# Fyve_Sicks.net
KiCad netlist of a schematic drawn in EAGLE
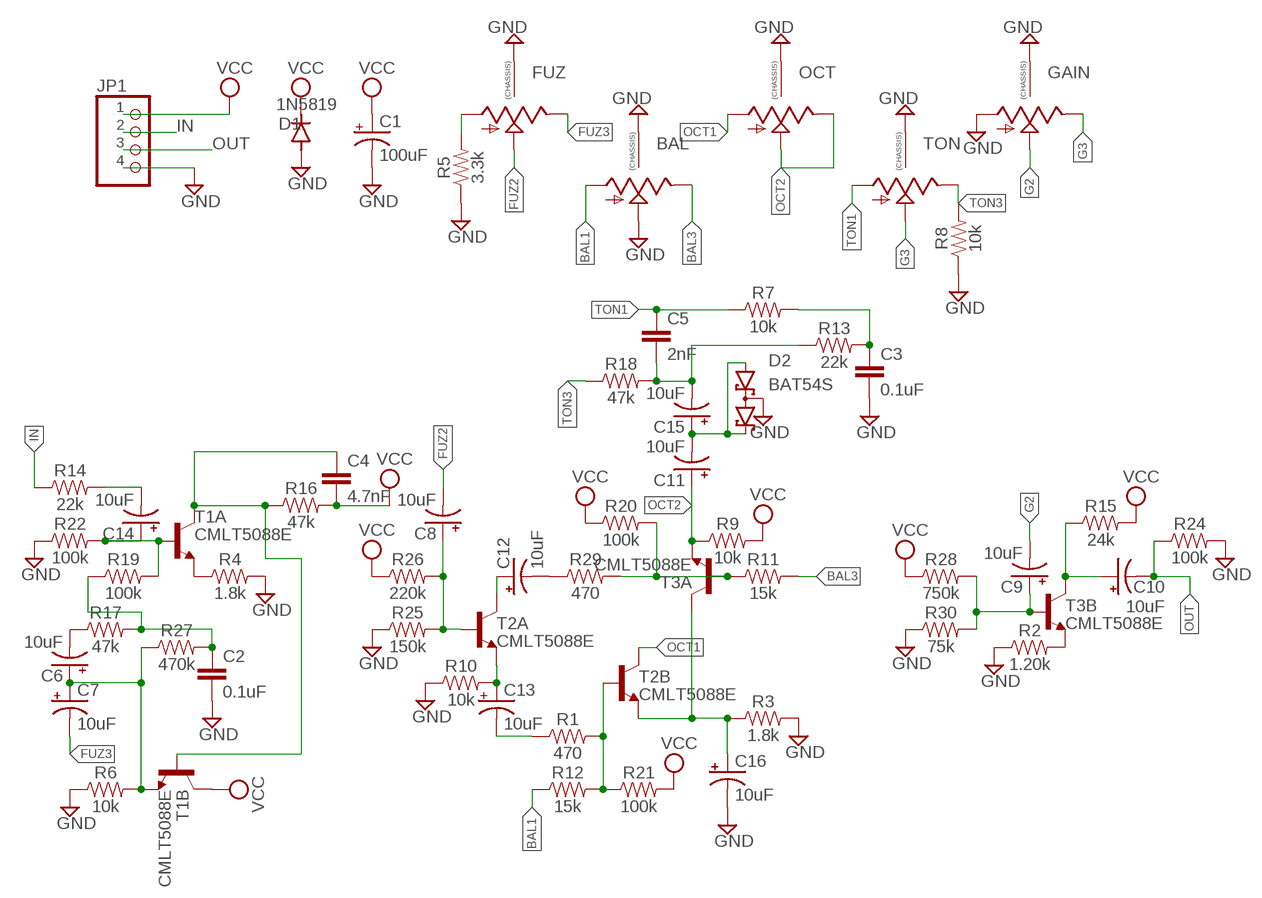
[diagram p0: schematic, sheet 1]

(export (version "E")
  (design (tool "Eeschema 10.0.6"))
  (components
    (comp (ref "BAL")
      (value "9MM_SNAP-IN_POT_CHASSIS")
      (footprint "eagle-import:9MM_SNAP-IN_POT")
      (libsource (lib "eagle-import") (part "9MM_SNAP-IN_POT_CHASSIS"))
    )
    (comp (ref "C1")
      (value "100uF")
      (footprint "eagle-import:PAN_B_SMD+THRU")
      (libsource (lib "eagle-import") (part "CAP_SMD+THRUPAN_B"))
    )
    (comp (ref "C2")
      (value "0.1uF")
      (footprint "eagle-import:0603")
      (libsource (lib "eagle-import") (part "0.1UF-0603-25V-(+80/-20%)"))
    )
    (comp (ref "C3")
      (value "0.1uF")
      (footprint "eagle-import:0603")
      (libsource (lib "eagle-import") (part "0.1UF-0603-25V-(+80/-20%)"))
    )
    (comp (ref "C4")
      (value "4.7nF")
      (footprint "eagle-import:0603")
      (libsource (lib "eagle-import") (part "4.7PF-0603-50V-5%"))
    )
    (comp (ref "C5")
      (value "2nF")
      (footprint "eagle-import:0603")
      (libsource (lib "eagle-import") (part "2.2NF/2200PF-0603-50V-10%"))
    )
    (comp (ref "C6")
      (value "10uF")
      (footprint "eagle-import:EIA3528")
      (libsource (lib "eagle-import") (part "10UF-POLAR-EIA3528-20V-10%(TANT)"))
    )
    (comp (ref "C7")
      (value "10uF")
      (footprint "eagle-import:EIA3528")
      (libsource (lib "eagle-import") (part "10UF-POLAR-EIA3528-20V-10%(TANT)"))
    )
    (comp (ref "C8")
      (value "10uF")
      (footprint "eagle-import:EIA3528")
      (libsource (lib "eagle-import") (part "10UF-POLAR-EIA3528-20V-10%(TANT)"))
    )
    (comp (ref "C9")
      (value "10uF")
      (footprint "eagle-import:EIA3528")
      (libsource (lib "eagle-import") (part "10UF-POLAR-EIA3528-20V-10%(TANT)"))
    )
    (comp (ref "C10")
      (value "10uF")
      (footprint "eagle-import:EIA3528")
      (libsource (lib "eagle-import") (part "10UF-POLAR-EIA3528-20V-10%(TANT)"))
    )
    (comp (ref "C11")
      (value "10uF")
      (footprint "eagle-import:EIA3528")
      (libsource (lib "eagle-import") (part "10UF-POLAR-EIA3528-20V-10%(TANT)"))
    )
    (comp (ref "C12")
      (value "10uF")
      (footprint "eagle-import:EIA3528")
      (libsource (lib "eagle-import") (part "10UF-POLAR-EIA3528-20V-10%(TANT)"))
    )
    (comp (ref "C13")
      (value "10uF")
      (footprint "eagle-import:EIA3528")
      (libsource (lib "eagle-import") (part "10UF-POLAR-EIA3528-20V-10%(TANT)"))
    )
    (comp (ref "C14")
      (value "10uF")
      (footprint "eagle-import:EIA3528")
      (libsource (lib "eagle-import") (part "10UF-POLAR-EIA3528-20V-10%(TANT)"))
    )
    (comp (ref "C15")
      (value "10uF")
      (footprint "eagle-import:EIA3528")
      (libsource (lib "eagle-import") (part "10UF-POLAR-EIA3528-20V-10%(TANT)"))
    )
    (comp (ref "C16")
      (value "10uF")
      (footprint "eagle-import:EIA3528")
      (libsource (lib "eagle-import") (part "10UF-POLAR-EIA3528-20V-10%(TANT)"))
    )
    (comp (ref "D1")
      (value "1N5819")
      (footprint "eagle-import:SOD123")
      (libsource (lib "eagle-import") (part "DIODE-SOD123"))
    )
    (comp (ref "D2")
      (value "BAT54S")
      (footprint "eagle-import:SOT23")
      (libsource (lib "eagle-import") (part "BAT54S"))
    )
    (comp (ref "FUZ")
      (value "9MM_SNAP-IN_POT_CHASSIS")
      (footprint "eagle-import:9MM_SNAP-IN_POT")
      (libsource (lib "eagle-import") (part "9MM_SNAP-IN_POT_CHASSIS"))
    )
    (comp (ref "GAIN")
      (value "9MM_SNAP-IN_POT_CHASSIS")
      (footprint "eagle-import:9MM_SNAP-IN_POT")
      (libsource (lib "eagle-import") (part "9MM_SNAP-IN_POT_CHASSIS"))
    )
    (comp (ref "JP1")
      (value "PINHD-1X4")
      (footprint "eagle-import:1X04")
      (libsource (lib "eagle-import") (part "PINHD-1X4"))
    )
    (comp (ref "OCT")
      (value "9MM_SNAP-IN_POT_CHASSIS")
      (footprint "eagle-import:9MM_SNAP-IN_POT")
      (libsource (lib "eagle-import") (part "9MM_SNAP-IN_POT_CHASSIS"))
    )
    (comp (ref "R1")
      (value "470")
      (footprint "eagle-import:0603")
      (libsource (lib "eagle-import") (part "470OHM-0603-1/10W-1%"))
    )
    (comp (ref "R2")
      (value "1.20k")
      (footprint "eagle-import:0603")
      (libsource (lib "eagle-import") (part "1.20KOHM-0603-1/10W-1%"))
    )
    (comp (ref "R3")
      (value "1.8k")
      (footprint "eagle-import:0603")
      (libsource (lib "eagle-import") (part "1.8KOHM-0603-1/10W-1%"))
    )
    (comp (ref "R4")
      (value "1.8k")
      (footprint "eagle-import:0603")
      (libsource (lib "eagle-import") (part "1.8KOHM-0603-1/10W-1%"))
    )
    (comp (ref "R5")
      (value "3.3k")
      (footprint "eagle-import:0603")
      (libsource (lib "eagle-import") (part "3.3KOHM-0603-1/10W-1%"))
    )
    (comp (ref "R6")
      (value "10k")
      (footprint "eagle-import:0603")
      (libsource (lib "eagle-import") (part "10KOHM-0603-1/10W-1%"))
    )
    (comp (ref "R7")
      (value "10k")
      (footprint "eagle-import:0603")
      (libsource (lib "eagle-import") (part "10KOHM-0603-1/10W-1%"))
    )
    (comp (ref "R8")
      (value "10k")
      (footprint "eagle-import:0603")
      (libsource (lib "eagle-import") (part "10KOHM-0603-1/10W-1%"))
    )
    (comp (ref "R9")
      (value "10k")
      (footprint "eagle-import:0603")
      (libsource (lib "eagle-import") (part "10KOHM-0603-1/10W-1%"))
    )
    (comp (ref "R10")
      (value "10k")
      (footprint "eagle-import:0603")
      (libsource (lib "eagle-import") (part "10KOHM-0603-1/10W-1%"))
    )
    (comp (ref "R11")
      (value "15k")
      (footprint "eagle-import:0603")
      (libsource (lib "eagle-import") (part "15KOHM-0603-1/10W-1%"))
    )
    (comp (ref "R12")
      (value "15k")
      (footprint "eagle-import:0603")
      (libsource (lib "eagle-import") (part "15KOHM-0603-1/10W-1%"))
    )
    (comp (ref "R13")
      (value "22k")
      (footprint "eagle-import:0603")
      (libsource (lib "eagle-import") (part "22KOHM-0603-1/10W-1%"))
    )
    (comp (ref "R14")
      (value "22k")
      (footprint "eagle-import:0603")
      (libsource (lib "eagle-import") (part "22KOHM-0603-1/10W-1%"))
    )
    (comp (ref "R15")
      (value "24k")
      (footprint "eagle-import:0603")
      (libsource (lib "eagle-import") (part "22KOHM-0603-1/10W-1%"))
    )
    (comp (ref "R16")
      (value "47k")
      (footprint "eagle-import:0603")
      (libsource (lib "eagle-import") (part "47KOHM-0603-1/10W-1%"))
    )
    (comp (ref "R17")
      (value "47k")
      (footprint "eagle-import:0603")
      (libsource (lib "eagle-import") (part "47KOHM-0603-1/10W-1%"))
    )
    (comp (ref "R18")
      (value "47k")
      (footprint "eagle-import:0603")
      (libsource (lib "eagle-import") (part "47KOHM-0603-1/10W-1%"))
    )
    (comp (ref "R19")
      (value "100k")
      (footprint "eagle-import:0603")
      (libsource (lib "eagle-import") (part "100KOHM-0603-1/10W-1%"))
    )
    (comp (ref "R20")
      (value "100k")
      (footprint "eagle-import:0603")
      (libsource (lib "eagle-import") (part "100KOHM-0603-1/10W-1%"))
    )
    (comp (ref "R21")
      (value "100k")
      (footprint "eagle-import:0603")
      (libsource (lib "eagle-import") (part "100KOHM-0603-1/10W-1%"))
    )
    (comp (ref "R22")
      (value "100k")
      (footprint "eagle-import:0603")
      (libsource (lib "eagle-import") (part "100KOHM-0603-1/10W-1%"))
    )
    (comp (ref "R24")
      (value "100k")
      (footprint "eagle-import:0603")
      (libsource (lib "eagle-import") (part "100KOHM-0603-1/10W-1%"))
    )
    (comp (ref "R25")
      (value "150k")
      (footprint "eagle-import:0603")
      (libsource (lib "eagle-import") (part "150KOHM-0603-1/10W-1%"))
    )
    (comp (ref "R26")
      (value "220k")
      (footprint "eagle-import:0603")
      (libsource (lib "eagle-import") (part "220KOHM-0603-1/10W-1%"))
    )
    (comp (ref "R27")
      (value "470k")
      (footprint "eagle-import:0603")
      (libsource (lib "eagle-import") (part "470OHM-0603-1/10W-1%"))
    )
    (comp (ref "R28")
      (value "750k")
      (footprint "eagle-import:0603")
      (libsource (lib "eagle-import") (part "750OHM-0603-1/10W-1%"))
    )
    (comp (ref "R29")
      (value "470")
      (footprint "eagle-import:0603")
      (libsource (lib "eagle-import") (part "470OHM-0603-1/10W-1%"))
    )
    (comp (ref "R30")
      (value "75k")
      (footprint "eagle-import:0603")
      (libsource (lib "eagle-import") (part "75KOHM-0603-1/10W-1%"))
    )
    (comp (ref "T1")
      (value "CMLT5088E")
      (footprint "eagle-import:SOT563")
      (libsource (lib "eagle-import") (part "CMLT5088E"))
    )
    (comp (ref "T2")
      (value "CMLT5088E")
      (footprint "eagle-import:SOT563")
      (libsource (lib "eagle-import") (part "CMLT5088E"))
    )
    (comp (ref "T3")
      (value "CMLT5088E")
      (footprint "eagle-import:SOT563")
      (libsource (lib "eagle-import") (part "CMLT5088E"))
    )
    (comp (ref "TON")
      (value "9MM_SNAP-IN_POT_CHASSIS")
      (footprint "eagle-import:9MM_SNAP-IN_POT")
      (libsource (lib "eagle-import") (part "9MM_SNAP-IN_POT_CHASSIS"))
    )
  )
  (nets
    (net (code "1") (name "BAL1") (class "Default")
      (node (ref "BAL") (pin "1") (pinfunction "A_1") (pintype "passive"))
      (node (ref "R12") (pin "1") (pinfunction "1_1") (pintype "passive"))
    )
    (net (code "2") (name "BAL3") (class "Default")
      (node (ref "BAL") (pin "3") (pinfunction "E_3") (pintype "passive"))
      (node (ref "R11") (pin "2") (pinfunction "2_2") (pintype "passive"))
    )
    (net (code "3") (name "FUZ2") (class "Default")
      (node (ref "C8") (pin "C") (pinfunction "-_C") (pintype "passive"))
      (node (ref "FUZ") (pin "2") (pinfunction "S_2") (pintype "passive"))
    )
    (net (code "4") (name "FUZ3") (class "Default")
      (node (ref "C7") (pin "C") (pinfunction "-_C") (pintype "passive"))
      (node (ref "FUZ") (pin "3") (pinfunction "E_3") (pintype "passive"))
    )
    (net (code "5") (name "G2") (class "Default")
      (node (ref "C9") (pin "C") (pinfunction "-_C") (pintype "passive"))
      (node (ref "GAIN") (pin "2") (pinfunction "S_2") (pintype "passive"))
    )
    (net (code "6") (name "G3") (class "Default")
      (node (ref "GAIN") (pin "3") (pinfunction "E_3") (pintype "passive"))
      (node (ref "TON") (pin "2") (pinfunction "S_2") (pintype "passive"))
    )
    (net (code "7") (name "GND") (class "Default")
      (node (ref "BAL") (pin "2") (pinfunction "S_2") (pintype "passive"))
      (node (ref "BAL") (pin "CHASSIS1") (pinfunction "P$1_CHASSIS1") (pintype "passive"))
      (node (ref "BAL") (pin "CHASSIS2") (pinfunction "P$1_CHASSIS2") (pintype "passive"))
      (node (ref "C1") (pin "-") (pinfunction "-_-") (pintype "passive"))
      (node (ref "C1") (pin "--") (pinfunction "-_--") (pintype "passive"))
      (node (ref "C16") (pin "C") (pinfunction "-_C") (pintype "passive"))
      (node (ref "C2") (pin "2") (pinfunction "2_2") (pintype "passive"))
      (node (ref "C3") (pin "2") (pinfunction "2_2") (pintype "passive"))
      (node (ref "D1") (pin "A") (pinfunction "A_A") (pintype "passive"))
      (node (ref "D2") (pin "3") (pinfunction "C1A2_3") (pintype "passive"))
      (node (ref "FUZ") (pin "CHASSIS1") (pinfunction "P$1_CHASSIS1") (pintype "passive"))
      (node (ref "FUZ") (pin "CHASSIS2") (pinfunction "P$1_CHASSIS2") (pintype "passive"))
      (node (ref "GAIN") (pin "1") (pinfunction "A_1") (pintype "passive"))
      (node (ref "GAIN") (pin "CHASSIS1") (pinfunction "P$1_CHASSIS1") (pintype "passive"))
      (node (ref "GAIN") (pin "CHASSIS2") (pinfunction "P$1_CHASSIS2") (pintype "passive"))
      (node (ref "JP1") (pin "4") (pinfunction "4_4") (pintype "passive"))
      (node (ref "OCT") (pin "CHASSIS1") (pinfunction "P$1_CHASSIS1") (pintype "passive"))
      (node (ref "OCT") (pin "CHASSIS2") (pinfunction "P$1_CHASSIS2") (pintype "passive"))
      (node (ref "R10") (pin "1") (pinfunction "1_1") (pintype "passive"))
      (node (ref "R2") (pin "1") (pinfunction "1_1") (pintype "passive"))
      (node (ref "R22") (pin "1") (pinfunction "1_1") (pintype "passive"))
      (node (ref "R24") (pin "2") (pinfunction "2_2") (pintype "passive"))
      (node (ref "R25") (pin "1") (pinfunction "1_1") (pintype "passive"))
      (node (ref "R3") (pin "2") (pinfunction "2_2") (pintype "passive"))
      (node (ref "R30") (pin "1") (pinfunction "1_1") (pintype "passive"))
      (node (ref "R4") (pin "2") (pinfunction "2_2") (pintype "passive"))
      (node (ref "R5") (pin "1") (pinfunction "1_1") (pintype "passive"))
      (node (ref "R6") (pin "1") (pinfunction "1_1") (pintype "passive"))
      (node (ref "R8") (pin "1") (pinfunction "1_1") (pintype "passive"))
      (node (ref "TON") (pin "CHASSIS1") (pinfunction "P$1_CHASSIS1") (pintype "passive"))
      (node (ref "TON") (pin "CHASSIS2") (pinfunction "P$1_CHASSIS2") (pintype "passive"))
    )
    (net (code "8") (name "IN") (class "Default")
      (node (ref "JP1") (pin "2") (pinfunction "2_2") (pintype "passive"))
      (node (ref "R14") (pin "1") (pinfunction "1_1") (pintype "passive"))
    )
    (net (code "9") (name "Net-(C2-Pad1)") (class "Default")
      (node (ref "C2") (pin "1") (pinfunction "1_1") (pintype "passive"))
      (node (ref "R17") (pin "2") (pinfunction "2_2") (pintype "passive"))
      (node (ref "R19") (pin "1") (pinfunction "1_1") (pintype "passive"))
      (node (ref "R27") (pin "2") (pinfunction "2_2") (pintype "passive"))
    )
    (net (code "10") (name "Net-(C3-Pad1)") (class "Default")
      (node (ref "C3") (pin "1") (pinfunction "1_1") (pintype "passive"))
      (node (ref "R13") (pin "2") (pinfunction "2_2") (pintype "passive"))
      (node (ref "R7") (pin "2") (pinfunction "2_2") (pintype "passive"))
    )
    (net (code "11") (name "Net-(C6-+)") (class "Default")
      (node (ref "C6") (pin "A") (pinfunction "+_A") (pintype "passive"))
      (node (ref "C7") (pin "A") (pinfunction "+_A") (pintype "passive"))
      (node (ref "R27") (pin "1") (pinfunction "1_1") (pintype "passive"))
      (node (ref "R6") (pin "2") (pinfunction "2_2") (pintype "passive"))
      (node (ref "T1") (pin "4") (pinfunction "E_4") (pintype "passive"))
    )
    (net (code "12") (name "Net-(C6--)") (class "Default")
      (node (ref "C6") (pin "C") (pinfunction "-_C") (pintype "passive"))
      (node (ref "R17") (pin "1") (pinfunction "1_1") (pintype "passive"))
    )
    (net (code "13") (name "Net-(C8-+)") (class "Default")
      (node (ref "C8") (pin "A") (pinfunction "+_A") (pintype "passive"))
      (node (ref "R25") (pin "2") (pinfunction "2_2") (pintype "passive"))
      (node (ref "R26") (pin "2") (pinfunction "2_2") (pintype "passive"))
      (node (ref "T2") (pin "2") (pinfunction "B_2") (pintype "passive"))
    )
    (net (code "14") (name "Net-(C9-+)") (class "Default")
      (node (ref "C9") (pin "A") (pinfunction "+_A") (pintype "passive"))
      (node (ref "R28") (pin "2") (pinfunction "2_2") (pintype "passive"))
      (node (ref "R30") (pin "2") (pinfunction "2_2") (pintype "passive"))
      (node (ref "T3") (pin "5") (pinfunction "B_5") (pintype "passive"))
    )
    (net (code "15") (name "Net-(C10-+)") (class "Default")
      (node (ref "C10") (pin "A") (pinfunction "+_A") (pintype "passive"))
      (node (ref "R15") (pin "1") (pinfunction "1_1") (pintype "passive"))
      (node (ref "T3") (pin "3") (pinfunction "C_3") (pintype "passive"))
    )
    (net (code "16") (name "Net-(C11--)") (class "Default")
      (node (ref "C11") (pin "C") (pinfunction "-_C") (pintype "passive"))
      (node (ref "C15") (pin "A") (pinfunction "+_A") (pintype "passive"))
      (node (ref "D2") (pin "1") (pinfunction "A1_1") (pintype "passive"))
      (node (ref "D2") (pin "2") (pinfunction "C2_2") (pintype "passive"))
    )
    (net (code "17") (name "Net-(C12-+)") (class "Default")
      (node (ref "C12") (pin "A") (pinfunction "+_A") (pintype "passive"))
      (node (ref "T2") (pin "6") (pinfunction "C_6") (pintype "passive"))
    )
    (net (code "18") (name "Net-(C12--)") (class "Default")
      (node (ref "C12") (pin "C") (pinfunction "-_C") (pintype "passive"))
      (node (ref "R29") (pin "1") (pinfunction "1_1") (pintype "passive"))
    )
    (net (code "19") (name "Net-(C13-+)") (class "Default")
      (node (ref "C13") (pin "A") (pinfunction "+_A") (pintype "passive"))
      (node (ref "R10") (pin "2") (pinfunction "2_2") (pintype "passive"))
      (node (ref "T2") (pin "1") (pinfunction "E_1") (pintype "passive"))
    )
    (net (code "20") (name "Net-(C13--)") (class "Default")
      (node (ref "C13") (pin "C") (pinfunction "-_C") (pintype "passive"))
      (node (ref "R1") (pin "1") (pinfunction "1_1") (pintype "passive"))
    )
    (net (code "21") (name "Net-(C14-+)") (class "Default")
      (node (ref "C14") (pin "A") (pinfunction "+_A") (pintype "passive"))
      (node (ref "R19") (pin "2") (pinfunction "2_2") (pintype "passive"))
      (node (ref "R22") (pin "2") (pinfunction "2_2") (pintype "passive"))
      (node (ref "T1") (pin "2") (pinfunction "B_2") (pintype "passive"))
    )
    (net (code "22") (name "Net-(C14--)") (class "Default")
      (node (ref "C14") (pin "C") (pinfunction "-_C") (pintype "passive"))
      (node (ref "R14") (pin "2") (pinfunction "2_2") (pintype "passive"))
    )
    (net (code "23") (name "Net-(C15--)") (class "Default")
      (node (ref "C15") (pin "C") (pinfunction "-_C") (pintype "passive"))
      (node (ref "C5") (pin "2") (pinfunction "2_2") (pintype "passive"))
      (node (ref "R13") (pin "1") (pinfunction "1_1") (pintype "passive"))
      (node (ref "R18") (pin "2") (pinfunction "2_2") (pintype "passive"))
    )
    (net (code "24") (name "Net-(C16-+)") (class "Default")
      (node (ref "C16") (pin "A") (pinfunction "+_A") (pintype "passive"))
      (node (ref "R3") (pin "1") (pinfunction "1_1") (pintype "passive"))
      (node (ref "T2") (pin "4") (pinfunction "E_4") (pintype "passive"))
      (node (ref "T3") (pin "6") (pinfunction "C_6") (pintype "passive"))
    )
    (net (code "25") (name "Net-(FUZ-A)") (class "Default")
      (node (ref "FUZ") (pin "1") (pinfunction "A_1") (pintype "passive"))
      (node (ref "R5") (pin "2") (pinfunction "2_2") (pintype "passive"))
    )
    (net (code "26") (name "Net-(T1A-C)") (class "Default")
      (node (ref "C4") (pin "1") (pinfunction "1_1") (pintype "passive"))
      (node (ref "R16") (pin "1") (pinfunction "1_1") (pintype "passive"))
      (node (ref "T1") (pin "5") (pinfunction "B_5") (pintype "passive"))
      (node (ref "T1") (pin "6") (pinfunction "C_6") (pintype "passive"))
    )
    (net (code "27") (name "Net-(T1A-E)") (class "Default")
      (node (ref "R4") (pin "1") (pinfunction "1_1") (pintype "passive"))
      (node (ref "T1") (pin "1") (pinfunction "E_1") (pintype "passive"))
    )
    (net (code "28") (name "Net-(T2B-B)") (class "Default")
      (node (ref "R1") (pin "2") (pinfunction "2_2") (pintype "passive"))
      (node (ref "R12") (pin "2") (pinfunction "2_2") (pintype "passive"))
      (node (ref "R21") (pin "1") (pinfunction "1_1") (pintype "passive"))
      (node (ref "T2") (pin "5") (pinfunction "B_5") (pintype "passive"))
    )
    (net (code "29") (name "Net-(T3A-B)") (class "Default")
      (node (ref "R11") (pin "1") (pinfunction "1_1") (pintype "passive"))
      (node (ref "R20") (pin "2") (pinfunction "2_2") (pintype "passive"))
      (node (ref "R29") (pin "2") (pinfunction "2_2") (pintype "passive"))
      (node (ref "T3") (pin "2") (pinfunction "B_2") (pintype "passive"))
    )
    (net (code "30") (name "Net-(T3B-E)") (class "Default")
      (node (ref "R2") (pin "2") (pinfunction "2_2") (pintype "passive"))
      (node (ref "T3") (pin "4") (pinfunction "E_4") (pintype "passive"))
    )
    (net (code "31") (name "OCT1") (class "Default")
      (node (ref "OCT") (pin "1") (pinfunction "A_1") (pintype "passive"))
      (node (ref "T2") (pin "3") (pinfunction "C_3") (pintype "passive"))
    )
    (net (code "32") (name "OCT2") (class "Default")
      (node (ref "C11") (pin "A") (pinfunction "+_A") (pintype "passive"))
      (node (ref "OCT") (pin "2") (pinfunction "S_2") (pintype "passive"))
      (node (ref "OCT") (pin "3") (pinfunction "E_3") (pintype "passive"))
      (node (ref "R9") (pin "1") (pinfunction "1_1") (pintype "passive"))
      (node (ref "T3") (pin "1") (pinfunction "E_1") (pintype "passive"))
    )
    (net (code "33") (name "OUT") (class "Default")
      (node (ref "C10") (pin "C") (pinfunction "-_C") (pintype "passive"))
      (node (ref "JP1") (pin "3") (pinfunction "3_3") (pintype "passive"))
      (node (ref "R24") (pin "1") (pinfunction "1_1") (pintype "passive"))
    )
    (net (code "34") (name "TON1") (class "Default")
      (node (ref "C5") (pin "1") (pinfunction "1_1") (pintype "passive"))
      (node (ref "R7") (pin "1") (pinfunction "1_1") (pintype "passive"))
      (node (ref "TON") (pin "1") (pinfunction "A_1") (pintype "passive"))
    )
    (net (code "35") (name "TON3") (class "Default")
      (node (ref "R18") (pin "1") (pinfunction "1_1") (pintype "passive"))
      (node (ref "R8") (pin "2") (pinfunction "2_2") (pintype "passive"))
      (node (ref "TON") (pin "3") (pinfunction "E_3") (pintype "passive"))
    )
    (net (code "36") (name "VCC") (class "Default")
      (node (ref "C1") (pin "+") (pinfunction "+_+") (pintype "passive"))
      (node (ref "C1") (pin "++") (pinfunction "+_++") (pintype "passive"))
      (node (ref "C4") (pin "2") (pinfunction "2_2") (pintype "passive"))
      (node (ref "D1") (pin "C") (pinfunction "C_C") (pintype "passive"))
      (node (ref "JP1") (pin "1") (pinfunction "1_1") (pintype "passive"))
      (node (ref "R15") (pin "2") (pinfunction "2_2") (pintype "passive"))
      (node (ref "R16") (pin "2") (pinfunction "2_2") (pintype "passive"))
      (node (ref "R20") (pin "1") (pinfunction "1_1") (pintype "passive"))
      (node (ref "R21") (pin "2") (pinfunction "2_2") (pintype "passive"))
      (node (ref "R26") (pin "1") (pinfunction "1_1") (pintype "passive"))
      (node (ref "R28") (pin "1") (pinfunction "1_1") (pintype "passive"))
      (node (ref "R9") (pin "2") (pinfunction "2_2") (pintype "passive"))
      (node (ref "T1") (pin "3") (pinfunction "C_3") (pintype "passive"))
    )
  )
)
